# FE_Channel.net
KiCad netlist of a schematic drawn in Altium Designer
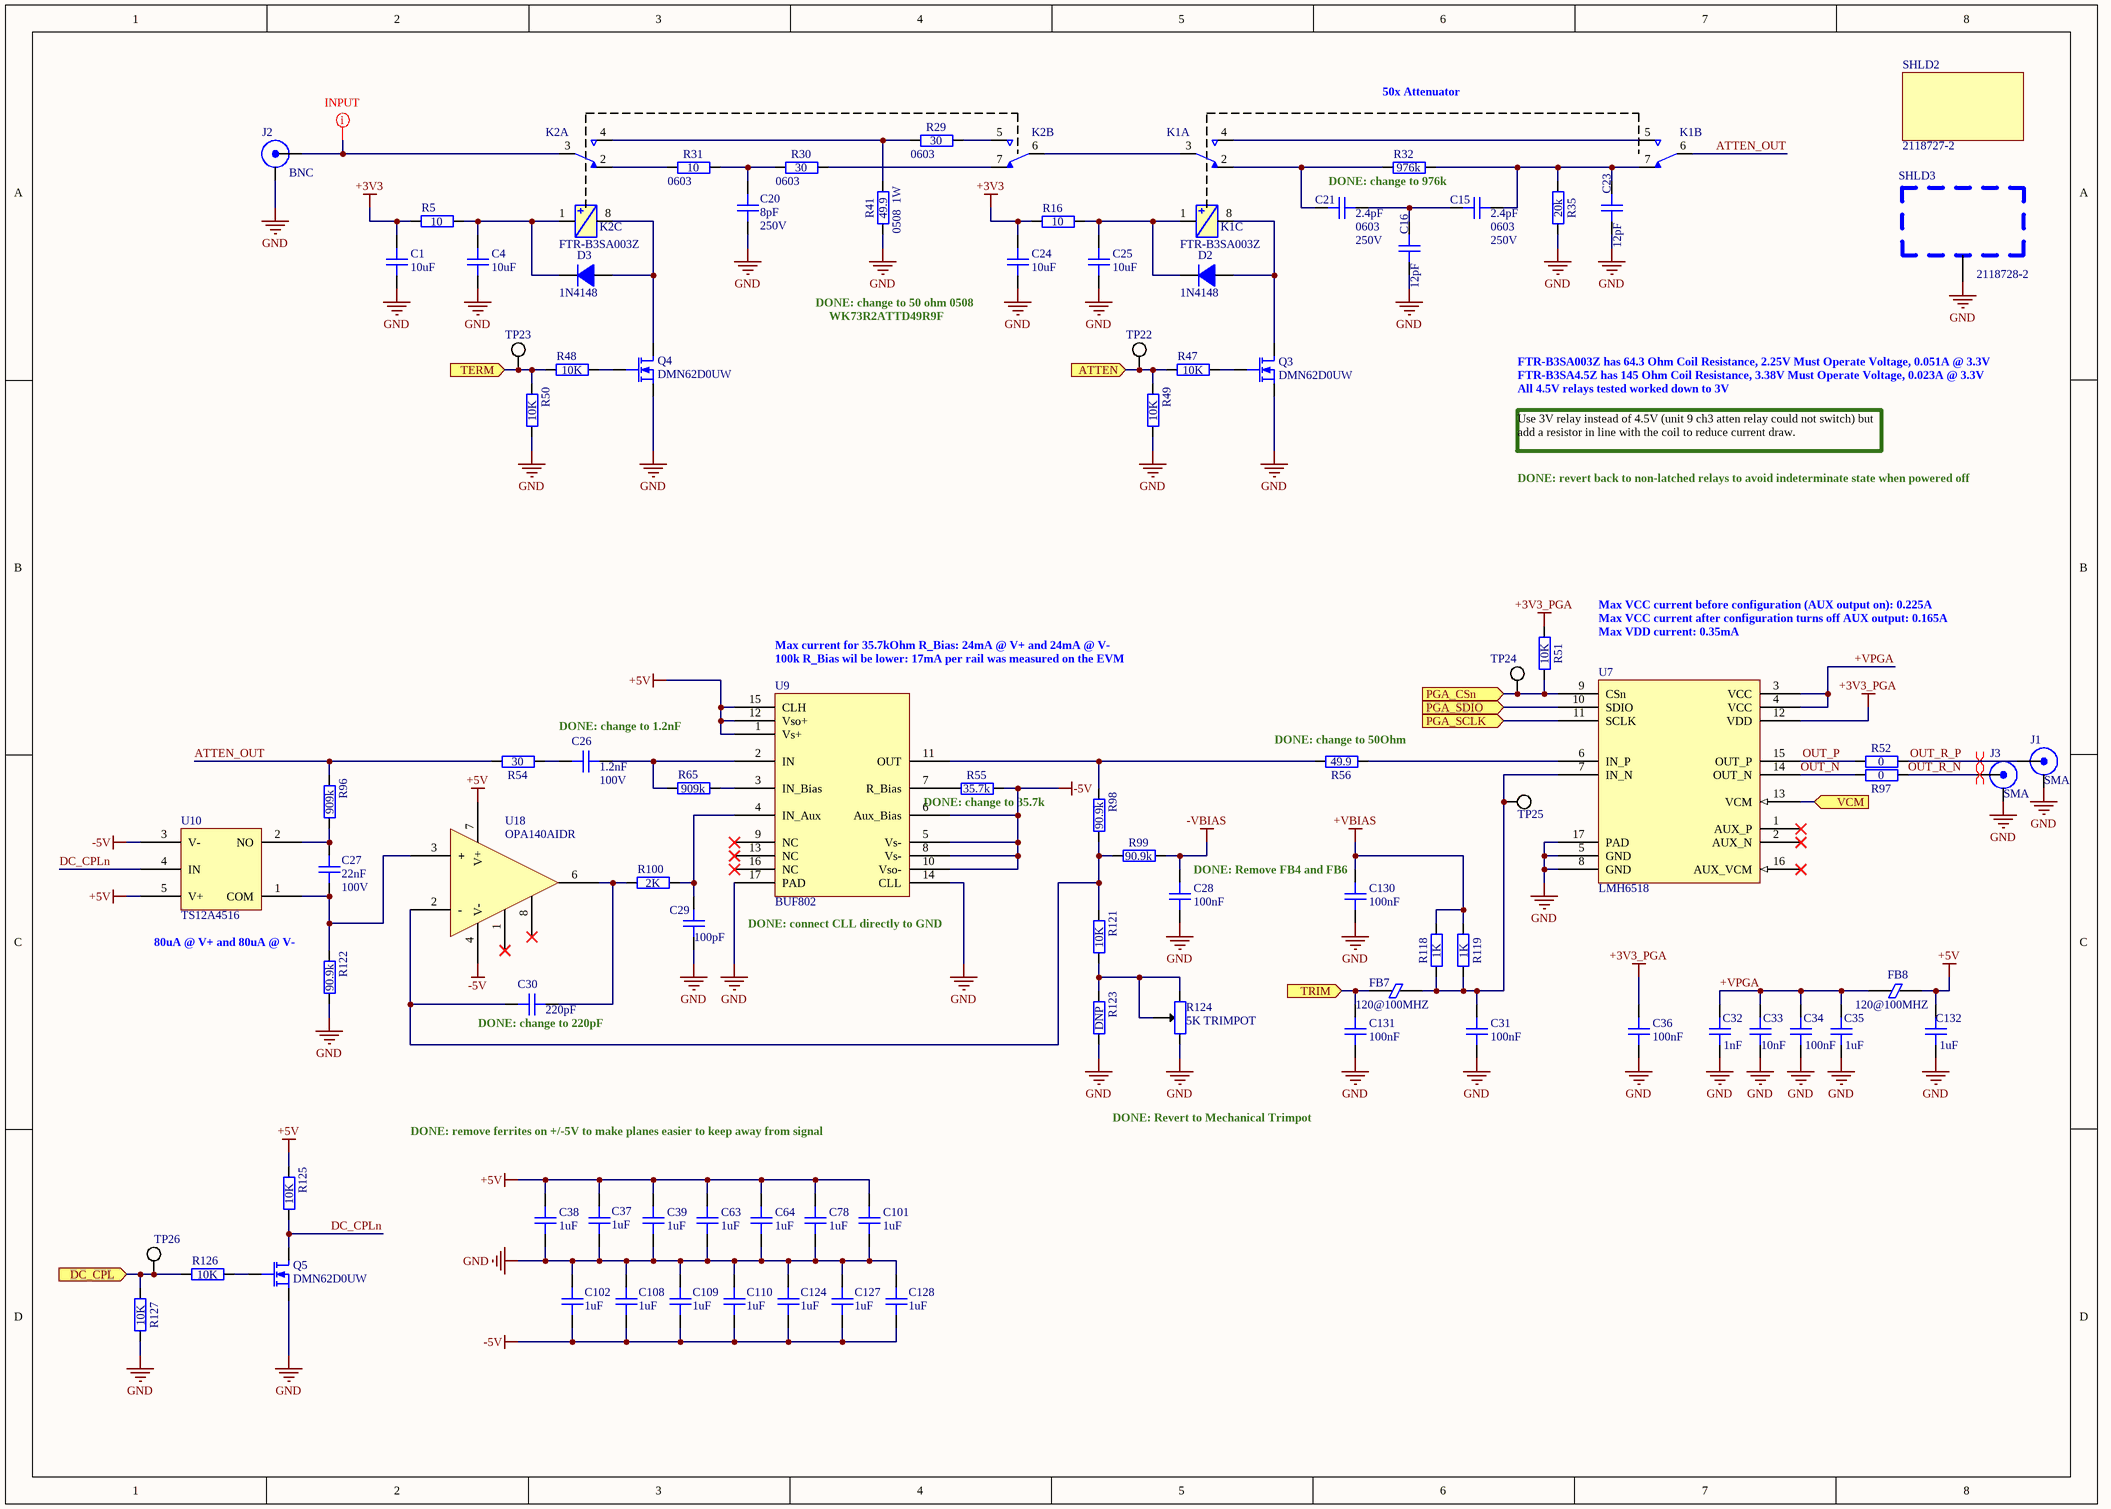
[diagram p0: FE_Channel.SchDoc]

(export (version "E")
  (design (tool "Eeschema 10.0.6"))
  (components
    (comp (ref "C1")
      (value "10uF")
      (footprint "GEN_C_0603")
      (fields
        (field (name "HOUSE PART NUMBER") "C-10uF-0603-002")
        (field (name "MANUFACTURER") "Murata")
        (field (name "MANUFACTURER PART NUMBER") "GRM188R61A106ME69D")
      )
      (libsource (lib "DSO") (part "CAP 10uF 10V X5R 0603"))
    )
    (comp (ref "C4")
      (value "10uF")
      (footprint "GEN_C_0603")
      (fields
        (field (name "HOUSE PART NUMBER") "C-10uF-0603-002")
        (field (name "MANUFACTURER") "Murata")
        (field (name "MANUFACTURER PART NUMBER") "GRM188R61A106ME69D")
      )
      (libsource (lib "DSO") (part "CAP 10uF 10V X5R 0603"))
    )
    (comp (ref "C15")
      (value "2.4pF")
      (footprint "GEN_C_0603")
      (fields
        (field (name "PACKAGE") "0603")
        (field (name "VOLTAGE RATING") "250V")
        (field (name "MANUFACTURER") "KEMET")
        (field (name "MANUFACTURER PART NUMBER") "CBR06C249BAGAC")
      )
      (libsource (lib "DSO") (part "CAP 2.4pF 250V C0G 0603"))
    )
    (comp (ref "C16")
      (value "12pF")
      (footprint "GEN_C_0402")
      (fields
        (field (name "MANUFACTURER") "KEMET")
        (field (name "MANUFACTURER PART NUMBER") "CBR04C120F5GAC")
      )
      (libsource (lib "DSO") (part "CAP 12pF 50V C0G 0402"))
    )
    (comp (ref "C20")
      (value "8pF")
      (footprint "GEN_C_0603")
      (fields
        (field (name "MANUFACTURER") "KEMET")
        (field (name "MANUFACTURER PART NUMBER") "CBR06C809BAGAC")
        (field (name "VOLTAGE RATING") "250V")
      )
      (libsource (lib "DSO") (part "CAP 8pF 250V C0G 0603"))
    )
    (comp (ref "C21")
      (value "2.4pF")
      (footprint "GEN_C_0603")
      (fields
        (field (name "PACKAGE") "0603")
        (field (name "VOLTAGE RATING") "250V")
        (field (name "MANUFACTURER") "KEMET")
        (field (name "MANUFACTURER PART NUMBER") "CBR06C249BAGAC")
      )
      (libsource (lib "DSO") (part "CAP 2.4pF 250V C0G 0603"))
    )
    (comp (ref "C23")
      (value "12pF")
      (footprint "GEN_C_0402")
      (fields
        (field (name "MANUFACTURER") "KEMET")
        (field (name "MANUFACTURER PART NUMBER") "CBR04C120F5GAC")
      )
      (libsource (lib "DSO") (part "CAP 12pF 50V C0G 0402"))
    )
    (comp (ref "C24")
      (value "10uF")
      (footprint "GEN_C_0603")
      (fields
        (field (name "HOUSE PART NUMBER") "C-10uF-0603-002")
        (field (name "MANUFACTURER") "Murata")
        (field (name "MANUFACTURER PART NUMBER") "GRM188R61A106ME69D")
      )
      (libsource (lib "DSO") (part "CAP 10uF 10V X5R 0603"))
    )
    (comp (ref "C25")
      (value "10uF")
      (footprint "GEN_C_0603")
      (fields
        (field (name "HOUSE PART NUMBER") "C-10uF-0603-002")
        (field (name "MANUFACTURER") "Murata")
        (field (name "MANUFACTURER PART NUMBER") "GRM188R61A106ME69D")
      )
      (libsource (lib "DSO") (part "CAP 10uF 10V X5R 0603"))
    )
    (comp (ref "C26")
      (value "1.2nF")
      (footprint "GEN_C_0603")
      (fields
        (field (name "VOLTAGE RATING") "100V")
        (field (name "MANUFACTURER") "Murata")
        (field (name "MANUFACTURER PART NUMBER") "GCM1885C2A122FA16D")
      )
      (libsource (lib "DSO") (part "CAP 1.2nF 100V C0G 0603"))
    )
    (comp (ref "C27")
      (value "22nF")
      (footprint "GEN_C_0603")
      (fields
        (field (name "VOLTAGE RATING") "100V")
        (field (name "MANUFACTURER") "Murata")
        (field (name "MANUFACTURER PART NUMBER") "GCM188R72A223KA37D")
      )
      (libsource (lib "DSO") (part "CAP 22nF 100V X7R 0603"))
    )
    (comp (ref "C28")
      (value "100nF")
      (footprint "GEN_C_0402")
      (fields
        (field (name "HOUSE PART NUMBER") "C-100nF-0402-002")
        (field (name "MANUFACTURER") "Murata")
        (field (name "MANUFACTURER PART NUMBER") "GCM155R71C104KA55D")
      )
      (libsource (lib "DSO") (part "CAP 100nF 16V X7R 0402"))
    )
    (comp (ref "C29")
      (value "100pF")
      (footprint "GEN_C_0402")
      (fields
        (field (name "MANUFACTURER") "Murata")
        (field (name "MANUFACTURER PART NUMBER") "GCM1555C1H101FA16D")
      )
      (libsource (lib "DSO") (part "CAP 100pF 50V C0G 0402"))
    )
    (comp (ref "C30")
      (value "220pF")
      (footprint "GEN_C_0402")
      (fields
        (field (name "MANUFACTURER") "Murata")
        (field (name "MANUFACTURER PART NUMBER") "GCM1555C1H221FA16J")
      )
      (libsource (lib "DSO") (part "CAP 220pF 50V C0G 0402"))
    )
    (comp (ref "C31")
      (value "100nF")
      (footprint "GEN_C_0402")
      (fields
        (field (name "HOUSE PART NUMBER") "C-100nF-0402-002")
        (field (name "MANUFACTURER") "Murata")
        (field (name "MANUFACTURER PART NUMBER") "GCM155R71C104KA55D")
      )
      (libsource (lib "DSO") (part "CAP 100nF 16V X7R 0402"))
    )
    (comp (ref "C32")
      (value "1nF")
      (footprint "GEN_C_0402")
      (fields
        (field (name "MANUFACTURER") "Murata")
        (field (name "MANUFACTURER PART NUMBER") "GRM1555C1H102FA01D")
      )
      (libsource (lib "DSO") (part "CAP 1nF 50V C0G 0402"))
    )
    (comp (ref "C33")
      (value "10nF")
      (footprint "GEN_C_0402")
      (fields
        (field (name "HOUSE PART NUMBER") "C-10nF-0402-002")
        (field (name "MANUFACTURER") "Murata")
        (field (name "MANUFACTURER PART NUMBER") "GRM155R71H103KA88J")
      )
      (libsource (lib "DSO") (part "CAP 10nF 50V X7R 0402"))
    )
    (comp (ref "C34")
      (value "100nF")
      (footprint "GEN_C_0402")
      (fields
        (field (name "HOUSE PART NUMBER") "C-100nF-0402-002")
        (field (name "MANUFACTURER") "Murata")
        (field (name "MANUFACTURER PART NUMBER") "GCM155R71C104KA55D")
      )
      (libsource (lib "DSO") (part "CAP 100nF 16V X7R 0402"))
    )
    (comp (ref "C35")
      (value "1uF")
      (footprint "GEN_C_0402")
      (fields
        (field (name "MANUFACTURER") "Murata")
        (field (name "MANUFACTURER PART NUMBER") "GRM155R61E105KA12D")
      )
      (libsource (lib "DSO") (part "CAP 1uF 25V X5R 0402"))
    )
    (comp (ref "C36")
      (value "100nF")
      (footprint "GEN_C_0402")
      (fields
        (field (name "HOUSE PART NUMBER") "C-100nF-0402-002")
        (field (name "MANUFACTURER") "Murata")
        (field (name "MANUFACTURER PART NUMBER") "GCM155R71C104KA55D")
      )
      (libsource (lib "DSO") (part "CAP 100nF 16V X7R 0402"))
    )
    (comp (ref "C37")
      (value "1uF")
      (footprint "GEN_C_0402")
      (fields
        (field (name "MANUFACTURER") "Murata")
        (field (name "MANUFACTURER PART NUMBER") "GRM155R61E105KA12D")
      )
      (libsource (lib "DSO") (part "CAP 1uF 25V X5R 0402"))
    )
    (comp (ref "C38")
      (value "1uF")
      (footprint "GEN_C_0402")
      (fields
        (field (name "MANUFACTURER") "Murata")
        (field (name "MANUFACTURER PART NUMBER") "GRM155R61E105KA12D")
      )
      (libsource (lib "DSO") (part "CAP 1uF 25V X5R 0402"))
    )
    (comp (ref "C39")
      (value "1uF")
      (footprint "GEN_C_0402")
      (fields
        (field (name "MANUFACTURER") "Murata")
        (field (name "MANUFACTURER PART NUMBER") "GRM155R61E105KA12D")
      )
      (libsource (lib "DSO") (part "CAP 1uF 25V X5R 0402"))
    )
    (comp (ref "C63")
      (value "1uF")
      (footprint "GEN_C_0402")
      (fields
        (field (name "MANUFACTURER") "Murata")
        (field (name "MANUFACTURER PART NUMBER") "GRM155R61E105KA12D")
      )
      (libsource (lib "DSO") (part "CAP 1uF 25V X5R 0402"))
    )
    (comp (ref "C64")
      (value "1uF")
      (footprint "GEN_C_0402")
      (fields
        (field (name "MANUFACTURER") "Murata")
        (field (name "MANUFACTURER PART NUMBER") "GRM155R61E105KA12D")
      )
      (libsource (lib "DSO") (part "CAP 1uF 25V X5R 0402"))
    )
    (comp (ref "C78")
      (value "1uF")
      (footprint "GEN_C_0402")
      (fields
        (field (name "MANUFACTURER") "Murata")
        (field (name "MANUFACTURER PART NUMBER") "GRM155R61E105KA12D")
      )
      (libsource (lib "DSO") (part "CAP 1uF 25V X5R 0402"))
    )
    (comp (ref "C101")
      (value "1uF")
      (footprint "GEN_C_0402")
      (fields
        (field (name "MANUFACTURER") "Murata")
        (field (name "MANUFACTURER PART NUMBER") "GRM155R61E105KA12D")
      )
      (libsource (lib "DSO") (part "CAP 1uF 25V X5R 0402"))
    )
    (comp (ref "C102")
      (value "1uF")
      (footprint "GEN_C_0402")
      (fields
        (field (name "MANUFACTURER") "Murata")
        (field (name "MANUFACTURER PART NUMBER") "GRM155R61E105KA12D")
      )
      (libsource (lib "DSO") (part "CAP 1uF 25V X5R 0402"))
    )
    (comp (ref "C108")
      (value "1uF")
      (footprint "GEN_C_0402")
      (fields
        (field (name "MANUFACTURER") "Murata")
        (field (name "MANUFACTURER PART NUMBER") "GRM155R61E105KA12D")
      )
      (libsource (lib "DSO") (part "CAP 1uF 25V X5R 0402"))
    )
    (comp (ref "C109")
      (value "1uF")
      (footprint "GEN_C_0402")
      (fields
        (field (name "MANUFACTURER") "Murata")
        (field (name "MANUFACTURER PART NUMBER") "GRM155R61E105KA12D")
      )
      (libsource (lib "DSO") (part "CAP 1uF 25V X5R 0402"))
    )
    (comp (ref "C110")
      (value "1uF")
      (footprint "GEN_C_0402")
      (fields
        (field (name "MANUFACTURER") "Murata")
        (field (name "MANUFACTURER PART NUMBER") "GRM155R61E105KA12D")
      )
      (libsource (lib "DSO") (part "CAP 1uF 25V X5R 0402"))
    )
    (comp (ref "C124")
      (value "1uF")
      (footprint "GEN_C_0402")
      (fields
        (field (name "MANUFACTURER") "Murata")
        (field (name "MANUFACTURER PART NUMBER") "GRM155R61E105KA12D")
      )
      (libsource (lib "DSO") (part "CAP 1uF 25V X5R 0402"))
    )
    (comp (ref "C127")
      (value "1uF")
      (footprint "GEN_C_0402")
      (fields
        (field (name "MANUFACTURER") "Murata")
        (field (name "MANUFACTURER PART NUMBER") "GRM155R61E105KA12D")
      )
      (libsource (lib "DSO") (part "CAP 1uF 25V X5R 0402"))
    )
    (comp (ref "C128")
      (value "1uF")
      (footprint "GEN_C_0402")
      (fields
        (field (name "MANUFACTURER") "Murata")
        (field (name "MANUFACTURER PART NUMBER") "GRM155R61E105KA12D")
      )
      (libsource (lib "DSO") (part "CAP 1uF 25V X5R 0402"))
    )
    (comp (ref "C130")
      (value "100nF")
      (footprint "GEN_C_0402")
      (fields
        (field (name "HOUSE PART NUMBER") "C-100nF-0402-002")
        (field (name "MANUFACTURER") "Murata")
        (field (name "MANUFACTURER PART NUMBER") "GCM155R71C104KA55D")
      )
      (libsource (lib "DSO") (part "CAP 100nF 16V X7R 0402"))
    )
    (comp (ref "C131")
      (value "100nF")
      (footprint "GEN_C_0402")
      (fields
        (field (name "HOUSE PART NUMBER") "C-100nF-0402-002")
        (field (name "MANUFACTURER") "Murata")
        (field (name "MANUFACTURER PART NUMBER") "GCM155R71C104KA55D")
      )
      (libsource (lib "DSO") (part "CAP 100nF 16V X7R 0402"))
    )
    (comp (ref "C132")
      (value "1uF")
      (footprint "GEN_C_0402")
      (fields
        (field (name "MANUFACTURER") "Murata")
        (field (name "MANUFACTURER PART NUMBER") "GRM155R61E105KA12D")
      )
      (libsource (lib "DSO") (part "CAP 1uF 25V X5R 0402"))
    )
    (comp (ref "D2")
      (value "1N4148")
      (footprint "GEN_SOD_323")
      (fields (field (name "MANUFACTURER") "Diodes") (field (name "MANUFACTURER PART NUMBER") "1N4148WS-7-F"))
      (libsource (lib "DSO") (part "DIODE 1N4148"))
    )
    (comp (ref "D3")
      (value "1N4148")
      (footprint "GEN_SOD_323")
      (fields (field (name "MANUFACTURER") "Diodes") (field (name "MANUFACTURER PART NUMBER") "1N4148WS-7-F"))
      (libsource (lib "DSO") (part "DIODE 1N4148"))
    )
    (comp (ref "FB7")
      (value "120@100MHZ")
      (footprint "GEN_R_0402")
      (fields (field (name "HOUSE PART NUMBER") "BLM15PX121SN1D") (field (name "MANUFACTURER") "Murata"))
      (libsource (lib "DSO") (part "FERRITE BEAD 120 OHM 0402"))
    )
    (comp (ref "FB8")
      (value "120@100MHZ")
      (footprint "GEN_R_0402")
      (fields (field (name "HOUSE PART NUMBER") "BLM15PX121SN1D") (field (name "MANUFACTURER") "Murata"))
      (libsource (lib "DSO") (part "FERRITE BEAD 120 OHM 0402"))
    )
    (comp (ref "J1")
      (value "SMA")
      (footprint "MOL_0733910083")
      (fields (field (name "MANUFACTURER") "Molex") (field (name "MANUFACTURER PART NUMBER") "73391-0083"))
      (libsource (lib "DSO") (part "SMA JACK R/A"))
    )
    (comp (ref "J2")
      (value "BNC")
      (footprint "MOL_0731000105")
      (fields (field (name "MANUFACTURER") "Molex") (field (name "MANUFACTURER PART NUMBER") "73100-0105"))
      (libsource (lib "DSO") (part "BNC JACK R/A"))
    )
    (comp (ref "J3")
      (value "SMA")
      (footprint "MOL_0733910083")
      (fields (field (name "MANUFACTURER") "Molex") (field (name "MANUFACTURER PART NUMBER") "73391-0083"))
      (libsource (lib "DSO") (part "SMA JACK R/A"))
    )
    (comp (ref "K1")
      (value "FTR-B3SA003Z")
      (footprint "FUJ_FTR-B3SA")
      (fields (field (name "MANUFACTURER") "Fujitsu"))
      (libsource (lib "") (part "RELAY DPDT-NO FTR-B3SA003Z_1"))
    )
    (comp (ref "K2")
      (value "FTR-B3SA003Z")
      (footprint "FUJ_FTR-B3SA")
      (fields (field (name "MANUFACTURER") "Fujitsu"))
      (libsource (lib "DSO") (part "RELAY DPDT-NO FTR-B3SA003Z"))
    )
    (comp (ref "Q3")
      (value "DMN62D0UW")
      (footprint "GEN_SOT_323")
      (fields (field (name "HOUSE PART NUMBER") "DMN62D0UW-7") (field (name "MANUFACTURER") "Diodes"))
      (libsource (lib "DSO") (part "NMOS DMN62D0UW"))
    )
    (comp (ref "Q4")
      (value "DMN62D0UW")
      (footprint "GEN_SOT_323")
      (fields (field (name "HOUSE PART NUMBER") "DMN62D0UW-7") (field (name "MANUFACTURER") "Diodes"))
      (libsource (lib "DSO") (part "NMOS DMN62D0UW"))
    )
    (comp (ref "Q5")
      (value "DMN62D0UW")
      (footprint "GEN_SOT_323")
      (fields (field (name "HOUSE PART NUMBER") "DMN62D0UW-7") (field (name "MANUFACTURER") "Diodes"))
      (libsource (lib "DSO") (part "NMOS DMN62D0UW"))
    )
    (comp (ref "R5")
      (value "10")
      (footprint "GEN_R_0603")
      (fields
        (field (name "TOLERANCE") "1%")
        (field (name "MANUFACTURER") "KOA Speer")
        (field (name "MANUFACTURER PART NUMBER") "SG73P1JTTD10R0F")
      )
      (libsource (lib "") (part "RES 10 OHM 1% 1/3W 0603_1"))
    )
    (comp (ref "R16")
      (value "10")
      (footprint "GEN_R_0603")
      (fields
        (field (name "TOLERANCE") "1%")
        (field (name "MANUFACTURER") "KOA Speer")
        (field (name "MANUFACTURER PART NUMBER") "SG73P1JTTD10R0F")
      )
      (libsource (lib "DSO") (part "RES 10 OHM 1% 1/3W 0603"))
    )
    (comp (ref "R29")
      (value "30")
      (footprint "GEN_R_0603")
      (fields
        (field (name "TOLERANCE") "1%")
        (field (name "PACKAGE") "0603")
        (field (name "MANUFACTURER") "KOA Speer")
        (field (name "MANUFACTURER PART NUMBER") "SG73P1JTTD30R0F")
      )
      (libsource (lib "DSO") (part "RES 30 OHM 1% 1/3W 0603"))
    )
    (comp (ref "R30")
      (value "30")
      (footprint "GEN_R_0603")
      (fields
        (field (name "TOLERANCE") "1%")
        (field (name "PACKAGE") "0603")
        (field (name "MANUFACTURER") "KOA Speer")
        (field (name "MANUFACTURER PART NUMBER") "SG73P1JTTD30R0F")
      )
      (libsource (lib "DSO") (part "RES 30 OHM 1% 1/3W 0603"))
    )
    (comp (ref "R31")
      (value "10")
      (footprint "GEN_R_0603")
      (fields
        (field (name "TOLERANCE") "1%")
        (field (name "PACKAGE") "0603")
        (field (name "MANUFACTURER") "KOA Speer")
        (field (name "MANUFACTURER PART NUMBER") "SG73P1JTTD10R0F")
      )
      (libsource (lib "DSO") (part "RES 10 OHM 1% 1/3W 0603"))
    )
    (comp (ref "R32")
      (value "976k")
      (footprint "GEN_R_0603")
      (fields
        (field (name "MANUFACTURER") "KOA Speer")
        (field (name "MANUFACTURER PART NUMBER") "RK73H1JTTD9763F")
        (field (name "TOLERANCE") "1%")
      )
      (libsource (lib "DSO") (part "RES 976k OHM 1% 1/10W 0603"))
    )
    (comp (ref "R35")
      (value "20k")
      (footprint "GEN_R_0402")
      (fields
        (field (name "TOLERANCE") "1%")
        (field (name "MANUFACTURER") "Yageo")
        (field (name "MANUFACTURER PART NUMBER") "RC0402FR-0720KL")
      )
      (libsource (lib "DSO") (part "RES 20K OHM 1% 1/16W 0402"))
    )
    (comp (ref "R41")
      (value "49.9")
      (footprint "GEN_R_0508")
      (fields
        (field (name "TOLERANCE") "1%")
        (field (name "PACKAGE") "0508")
        (field (name "MANUFACTURER") "KOA Speer")
        (field (name "MANUFACTURER PART NUMBER") "WK73R2ATTD49R9F")
        (field (name "POWER RATING") "1W")
      )
      (libsource (lib "DSO") (part "RES 49.9 OHM 1% 1W 0508"))
    )
    (comp (ref "R47")
      (value "10K")
      (footprint "GEN_R_0402")
      (fields
        (field (name "TOLERANCE") "1%")
        (field (name "MANUFACTURER") "Panasonic")
        (field (name "MANUFACTURER PART NUMBER") "ERJ-2RKF1002X")
      )
      (libsource (lib "DSO") (part "RES 10K OHM 1% 1/10W 0402"))
    )
    (comp (ref "R48")
      (value "10K")
      (footprint "GEN_R_0402")
      (fields
        (field (name "TOLERANCE") "1%")
        (field (name "MANUFACTURER") "Panasonic")
        (field (name "MANUFACTURER PART NUMBER") "ERJ-2RKF1002X")
      )
      (libsource (lib "DSO") (part "RES 10K OHM 1% 1/10W 0402"))
    )
    (comp (ref "R49")
      (value "10K")
      (footprint "GEN_R_0402")
      (fields
        (field (name "TOLERANCE") "1%")
        (field (name "MANUFACTURER") "Panasonic")
        (field (name "MANUFACTURER PART NUMBER") "ERJ-2RKF1002X")
      )
      (libsource (lib "") (part "RES 10K OHM 1% 1/10W 0402_1"))
    )
    (comp (ref "R50")
      (value "10K")
      (footprint "GEN_R_0402")
      (fields
        (field (name "TOLERANCE") "1%")
        (field (name "MANUFACTURER") "Panasonic")
        (field (name "MANUFACTURER PART NUMBER") "ERJ-2RKF1002X")
      )
      (libsource (lib "") (part "RES 10K OHM 1% 1/10W 0402_1"))
    )
    (comp (ref "R51")
      (value "10K")
      (footprint "GEN_R_0402")
      (fields
        (field (name "TOLERANCE") "1%")
        (field (name "MANUFACTURER") "Panasonic")
        (field (name "MANUFACTURER PART NUMBER") "ERJ-2RKF1002X")
      )
      (libsource (lib "") (part "RES 10K OHM 1% 1/10W 0402_1"))
    )
    (comp (ref "R52")
      (value "0")
      (footprint "GEN_R_0402")
      (fields
        (field (name "MANUFACTURER") "Yageo")
        (field (name "MANUFACTURER PART NUMBER") "RC0402JR-070RL")
      )
      (libsource (lib "DSO") (part "RES 0 OHM 1/16W 0402"))
    )
    (comp (ref "R54")
      (value "30")
      (footprint "GEN_R_0603")
      (fields
        (field (name "TOLERANCE") "1%")
        (field (name "MANUFACTURER") "KOA Speer")
        (field (name "MANUFACTURER PART NUMBER") "SG73P1JTTD30R0F")
      )
      (libsource (lib "DSO") (part "RES 30 OHM 1% 1/3W 0603"))
    )
    (comp (ref "R55")
      (value "35.7k")
      (footprint "GEN_R_0402")
      (fields
        (field (name "TOLERANCE") "1%")
        (field (name "MANUFACTURER") "Yageo")
        (field (name "MANUFACTURER PART NUMBER") "RC0402FR-0735K7L")
      )
      (libsource (lib "DSO") (part "RES 35.7K OHM 1% 1/16W 0402"))
    )
    (comp (ref "R56")
      (value "49.9")
      (footprint "GEN_R_0402")
      (fields
        (field (name "MANUFACTURER") "Yageo")
        (field (name "MANUFACTURER PART NUMBER") "RC0402FR-0749R9L")
        (field (name "TOLERANCE") "1%")
      )
      (libsource (lib "DSO") (part "RES 49.9 OHM 1% 1/10W 0402"))
    )
    (comp (ref "R65")
      (value "909k")
      (footprint "GEN_R_0402")
      (fields
        (field (name "TOLERANCE") "1%")
        (field (name "MANUFACTURER") "Yageo")
        (field (name "MANUFACTURER PART NUMBER") "RC0402FR-07909KL")
      )
      (libsource (lib "") (part "RES 909K OHM 1% 1/16W 0402_1"))
    )
    (comp (ref "R96")
      (value "909k")
      (footprint "GEN_R_0402")
      (fields
        (field (name "TOLERANCE") "1%")
        (field (name "MANUFACTURER") "Yageo")
        (field (name "MANUFACTURER PART NUMBER") "RC0402FR-07909KL")
      )
      (libsource (lib "DSO") (part "RES 909K OHM 1% 1/16W 0402"))
    )
    (comp (ref "R97")
      (value "0")
      (footprint "GEN_R_0402")
      (fields
        (field (name "MANUFACTURER") "Yageo")
        (field (name "MANUFACTURER PART NUMBER") "RC0402JR-070RL")
      )
      (libsource (lib "DSO") (part "RES 0 OHM 1/16W 0402"))
    )
    (comp (ref "R98")
      (value "90.9k")
      (footprint "GEN_R_0402")
      (fields
        (field (name "TOLERANCE") "1%")
        (field (name "MANUFACTURER") "Yageo")
        (field (name "MANUFACTURER PART NUMBER") "RC0402FR-0790K9L")
      )
      (libsource (lib "DSO") (part "RES 90.9K OHM 1% 1/16W 0402"))
    )
    (comp (ref "R99")
      (value "90.9k")
      (footprint "GEN_R_0402")
      (fields
        (field (name "TOLERANCE") "1%")
        (field (name "MANUFACTURER") "Yageo")
        (field (name "MANUFACTURER PART NUMBER") "RC0402FR-0790K9L")
      )
      (libsource (lib "") (part "RES 90.9K OHM 1% 1/16W 0402_1"))
    )
    (comp (ref "R100")
      (value "2K")
      (footprint "GEN_R_0402")
      (fields
        (field (name "TOLERANCE") "1%")
        (field (name "MANUFACTURER") "Yageo")
        (field (name "MANUFACTURER PART NUMBER") "RC0402FR-072KL")
      )
      (libsource (lib "DSO") (part "RES 2K OHM 1% 1/16W 0402"))
    )
    (comp (ref "R118")
      (value "1K")
      (footprint "GEN_R_0402")
      (fields
        (field (name "TOLERANCE") "1%")
        (field (name "HOUSE PART NUMBER") "R-1K-0402-1%-001")
        (field (name "MANUFACTURER") "Yageo")
      )
      (libsource (lib "DSO") (part "RES 1K OHM 1% 1/10W 0402"))
    )
    (comp (ref "R119")
      (value "1K")
      (footprint "GEN_R_0402")
      (fields
        (field (name "TOLERANCE") "1%")
        (field (name "HOUSE PART NUMBER") "R-1K-0402-1%-001")
        (field (name "MANUFACTURER") "Yageo")
      )
      (libsource (lib "") (part "RES 1K OHM 1% 1/10W 0402_1"))
    )
    (comp (ref "R121")
      (value "10K")
      (footprint "GEN_R_0402")
      (fields
        (field (name "TOLERANCE") "1%")
        (field (name "MANUFACTURER") "Panasonic")
        (field (name "MANUFACTURER PART NUMBER") "ERJ-2RKF1002X")
      )
      (libsource (lib "") (part "RES 10K OHM 1% 1/10W 0402_1"))
    )
    (comp (ref "R122")
      (value "90.9k")
      (footprint "GEN_R_0402")
      (fields
        (field (name "TOLERANCE") "1%")
        (field (name "MANUFACTURER") "Yageo")
        (field (name "MANUFACTURER PART NUMBER") "RC0402FR-0790K9L")
      )
      (libsource (lib "DSO") (part "RES 90.9K OHM 1% 1/16W 0402"))
    )
    (comp (ref "R123")
      (value "DNP")
      (footprint "GEN_R_0402")
      (fields (field (name "TOLERANCE") "1%"))
      (libsource (lib "DSO") (part "RES DNP 0402"))
    )
    (comp (ref "R124")
      (value "5K TRIMPOT")
      (footprint "BOU_3mm_POT")
      (fields
        (field (name "TOLERANCE") "1%")
        (field (name "MANUFACTURER") "Bourns")
        (field (name "MANUFACTURER PART NUMBER") "TC33X-2-502E")
      )
      (libsource (lib "DSO") (part "TRIMMER 5K OHM 0.1W J LEAD TOP"))
    )
    (comp (ref "R125")
      (value "10K")
      (footprint "GEN_R_0402")
      (fields
        (field (name "TOLERANCE") "1%")
        (field (name "MANUFACTURER") "Panasonic")
        (field (name "MANUFACTURER PART NUMBER") "ERJ-2RKF1002X")
      )
      (libsource (lib "") (part "RES 10K OHM 1% 1/10W 0402_1"))
    )
    (comp (ref "R126")
      (value "10K")
      (footprint "GEN_R_0402")
      (fields
        (field (name "TOLERANCE") "1%")
        (field (name "MANUFACTURER") "Panasonic")
        (field (name "MANUFACTURER PART NUMBER") "ERJ-2RKF1002X")
      )
      (libsource (lib "DSO") (part "RES 10K OHM 1% 1/10W 0402"))
    )
    (comp (ref "R127")
      (value "10K")
      (footprint "GEN_R_0402")
      (fields
        (field (name "TOLERANCE") "1%")
        (field (name "MANUFACTURER") "Panasonic")
        (field (name "MANUFACTURER PART NUMBER") "ERJ-2RKF1002X")
      )
      (libsource (lib "") (part "RES 10K OHM 1% 1/10W 0402_2"))
    )
    (comp (ref "SHLD2")
      (value "2118727-2")
      (fields (field (name "MANUFACTURER") "TE Connectivity AMP"))
      (libsource (lib "DSO") (part "SHIELD 2118727-2"))
    )
    (comp (ref "SHLD3")
      (value "2118728-2")
      (footprint "TE_2118728-2")
      (fields (field (name "MANUFACTURER") "TE Connectivity"))
      (libsource (lib "DSO") (part "SHIELD 2118728-2"))
    )
    (comp (ref "TP22") (value "PCB") (footprint "GEN_TP_PCB") (libsource (lib "DSO") (part "TP PCB 1mm")))
    (comp (ref "TP23") (value "PCB") (footprint "GEN_TP_PCB") (libsource (lib "DSO") (part "TP PCB 1mm")))
    (comp (ref "TP24") (value "PCB") (footprint "GEN_TP_PCB") (libsource (lib "DSO") (part "TP PCB 1mm")))
    (comp (ref "TP25") (value "PCB") (footprint "GEN_TP_PCB") (libsource (lib "DSO") (part "TP PCB 1mm")))
    (comp (ref "TP26") (value "PCB") (footprint "GEN_TP_PCB") (libsource (lib "DSO") (part "TP PCB 1mm")))
    (comp (ref "U7")
      (value "LMH6518")
      (footprint "TI_WQFN_RGH0016A")
      (fields
        (field (name "MANUFACTURER") "Texas Instruments")
        (field (name "MANUFACTURER PART NUMBER") "LMH6518SQE/NOPB")
      )
      (libsource (lib "DSO") (part "IC PGA LMH6518"))
    )
    (comp (ref "U9")
      (value "BUF802")
      (footprint "TI_VQFN_RGT0016C")
      (fields
        (field (name "MANUFACTURER") "Texas Instruments")
        (field (name "MANUFACTURER PART NUMBER") "BUF802IRGTR")
      )
      (libsource (lib "DSO") (part "IC BUFFER AMP BUF802"))
    )
    (comp (ref "U10")
      (value "TS12A4516")
      (footprint "GEN_SOT23_5_950_2900X1600X1450")
      (fields
        (field (name "MANUFACTURER") "Texas Instruments")
        (field (name "MANUFACTURER PART NUMBER") "TS12A4516DBVR")
      )
      (libsource (lib "DSO") (part "IC SWITCH SPST TS12A4516DBVR"))
    )
    (comp (ref "U18")
      (value "OPA140AIDR")
      (footprint "TI_SOIC8_D0008A")
      (fields (field (name "MANUFACTURER") "Texas Instruments"))
      (libsource (lib "DSO") (part "IC OPAMP OPA140"))
    )
  )
  (nets
    (net (code "1") (name "+3V3") (class "Default")
      (node (ref "C1") (pin "2") (pinfunction "2_2") (pintype "passive"))
      (node (ref "C24") (pin "2") (pinfunction "2_2") (pintype "passive"))
      (node (ref "R16") (pin "1") (pinfunction "1_1") (pintype "passive"))
      (node (ref "R5") (pin "2") (pinfunction "2_2") (pintype "passive"))
    )
    (net (code "2") (name "+3V3_PGA") (class "Default")
      (node (ref "C36") (pin "2") (pinfunction "2_2") (pintype "passive"))
      (node (ref "R51") (pin "2") (pinfunction "2_2") (pintype "passive"))
      (node (ref "U7") (pin "12") (pinfunction "VDD_12") (pintype "power_in"))
    )
    (net (code "3") (name "+5V") (class "Default")
      (node (ref "C101") (pin "2") (pinfunction "2_2") (pintype "passive"))
      (node (ref "C132") (pin "2") (pinfunction "2_2") (pintype "passive"))
      (node (ref "C37") (pin "2") (pinfunction "2_2") (pintype "passive"))
      (node (ref "C38") (pin "1") (pinfunction "1_1") (pintype "passive"))
      (node (ref "C39") (pin "1") (pinfunction "1_1") (pintype "passive"))
      (node (ref "C63") (pin "1") (pinfunction "1_1") (pintype "passive"))
      (node (ref "C64") (pin "2") (pinfunction "2_2") (pintype "passive"))
      (node (ref "C78") (pin "2") (pinfunction "2_2") (pintype "passive"))
      (node (ref "FB8") (pin "2") (pinfunction "2_2") (pintype "passive"))
      (node (ref "R125") (pin "2") (pinfunction "2_2") (pintype "passive"))
      (node (ref "U10") (pin "5") (pinfunction "V+_5") (pintype "passive"))
      (node (ref "U18") (pin "7") (pinfunction "V+_7") (pintype "passive"))
      (node (ref "U9") (pin "1") (pinfunction "Vs+_1") (pintype "passive"))
      (node (ref "U9") (pin "12") (pinfunction "Vso+_12") (pintype "passive"))
      (node (ref "U9") (pin "15") (pinfunction "CLH_15") (pintype "passive"))
    )
    (net (code "4") (name "+VBIAS") (class "Default")
      (node (ref "C130") (pin "1") (pinfunction "1_1") (pintype "passive"))
      (node (ref "R118") (pin "2") (pinfunction "2_2") (pintype "passive"))
      (node (ref "R119") (pin "1") (pinfunction "1_1") (pintype "passive"))
    )
    (net (code "5") (name "-5V") (class "Default")
      (node (ref "C102") (pin "2") (pinfunction "2_2") (pintype "passive"))
      (node (ref "C108") (pin "2") (pinfunction "2_2") (pintype "passive"))
      (node (ref "C109") (pin "1") (pinfunction "1_1") (pintype "passive"))
      (node (ref "C110") (pin "1") (pinfunction "1_1") (pintype "passive"))
      (node (ref "C124") (pin "1") (pinfunction "1_1") (pintype "passive"))
      (node (ref "C127") (pin "2") (pinfunction "2_2") (pintype "passive"))
      (node (ref "C128") (pin "2") (pinfunction "2_2") (pintype "passive"))
      (node (ref "R55") (pin "2") (pinfunction "2_2") (pintype "passive"))
      (node (ref "U10") (pin "3") (pinfunction "V-_3") (pintype "passive"))
      (node (ref "U18") (pin "4") (pinfunction "V-_4") (pintype "passive"))
      (node (ref "U9") (pin "10") (pinfunction "Vso-_10") (pintype "passive"))
      (node (ref "U9") (pin "5") (pinfunction "Vs-_5") (pintype "passive"))
      (node (ref "U9") (pin "6") (pinfunction "Aux_Bias_6") (pintype "passive"))
      (node (ref "U9") (pin "8") (pinfunction "Vs-_8") (pintype "passive"))
    )
    (net (code "6") (name "-VBIAS") (class "Default")
      (node (ref "C28") (pin "1") (pinfunction "1_1") (pintype "passive"))
      (node (ref "R99") (pin "1") (pinfunction "1_1") (pintype "passive"))
    )
    (net (code "7") (name "/+VPGA") (class "Default")
      (node (ref "C32") (pin "2") (pinfunction "2_2") (pintype "passive"))
      (node (ref "C33") (pin "2") (pinfunction "2_2") (pintype "passive"))
      (node (ref "C34") (pin "2") (pinfunction "2_2") (pintype "passive"))
      (node (ref "C35") (pin "2") (pinfunction "2_2") (pintype "passive"))
      (node (ref "FB8") (pin "1") (pinfunction "1_1") (pintype "passive"))
      (node (ref "U7") (pin "3") (pinfunction "VCC_3") (pintype "power_in"))
      (node (ref "U7") (pin "4") (pinfunction "VCC_4") (pintype "power_in"))
    )
    (net (code "8") (name "/ATTEN") (class "Default")
      (node (ref "R47") (pin "2") (pinfunction "2_2") (pintype "passive"))
      (node (ref "R49") (pin "2") (pinfunction "2_2") (pintype "passive"))
      (node (ref "TP22") (pin "1") (pinfunction "1_1") (pintype "passive"))
    )
    (net (code "9") (name "/ATTEN_OUT") (class "Default")
      (node (ref "K1") (pin "6") (pinfunction "6_6") (pintype "passive"))
      (node (ref "R54") (pin "1") (pinfunction "1_1") (pintype "passive"))
      (node (ref "R96") (pin "2") (pinfunction "2_2") (pintype "passive"))
    )
    (net (code "10") (name "/DC_CPL") (class "Default")
      (node (ref "R126") (pin "2") (pinfunction "2_2") (pintype "passive"))
      (node (ref "R127") (pin "2") (pinfunction "2_2") (pintype "passive"))
      (node (ref "TP26") (pin "1") (pinfunction "1_1") (pintype "passive"))
    )
    (net (code "11") (name "/DC_CPLn") (class "Default")
      (node (ref "Q5") (pin "1") (pinfunction "D_1") (pintype "passive"))
      (node (ref "R125") (pin "1") (pinfunction "1_1") (pintype "passive"))
      (node (ref "U10") (pin "4") (pinfunction "IN_4") (pintype "passive"))
    )
    (net (code "12") (name "/OUT_N") (class "Default")
      (node (ref "R97") (pin "1") (pinfunction "1_1") (pintype "passive"))
      (node (ref "U7") (pin "14") (pinfunction "OUT_N_14") (pintype "passive"))
    )
    (net (code "13") (name "/OUT_P") (class "Default")
      (node (ref "R52") (pin "1") (pinfunction "1_1") (pintype "passive"))
      (node (ref "U7") (pin "15") (pinfunction "OUT_P_15") (pintype "passive"))
    )
    (net (code "14") (name "/OUT_R_N") (class "Default")
      (node (ref "J3") (pin "1") (pinfunction "Signal_1") (pintype "passive"))
      (node (ref "R97") (pin "2") (pinfunction "2_2") (pintype "passive"))
    )
    (net (code "15") (name "/OUT_R_P") (class "Default")
      (node (ref "J1") (pin "1") (pinfunction "Signal_1") (pintype "passive"))
      (node (ref "R52") (pin "2") (pinfunction "2_2") (pintype "passive"))
    )
    (net (code "16") (name "/PGA_CSn") (class "Default")
      (node (ref "R51") (pin "1") (pinfunction "1_1") (pintype "passive"))
      (node (ref "TP24") (pin "1") (pinfunction "1_1") (pintype "passive"))
      (node (ref "U7") (pin "9") (pinfunction "CSn_9") (pintype "passive"))
    )
    (net (code "17") (name "/PGA_SCLK") (class "Default")
      (node (ref "U7") (pin "11") (pinfunction "SCLK_11") (pintype "passive"))
    )
    (net (code "18") (name "/PGA_SDIO") (class "Default")
      (node (ref "U7") (pin "10") (pinfunction "SDIO_10") (pintype "passive"))
    )
    (net (code "19") (name "/TERM") (class "Default")
      (node (ref "R48") (pin "2") (pinfunction "2_2") (pintype "passive"))
      (node (ref "R50") (pin "2") (pinfunction "2_2") (pintype "passive"))
      (node (ref "TP23") (pin "1") (pinfunction "1_1") (pintype "passive"))
    )
    (net (code "20") (name "/TRIM") (class "Default")
      (node (ref "C131") (pin "1") (pinfunction "1_1") (pintype "passive"))
      (node (ref "FB7") (pin "1") (pinfunction "1_1") (pintype "passive"))
    )
    (net (code "21") (name "/VCM") (class "Default")
      (node (ref "U7") (pin "13") (pinfunction "VCM_13") (pintype "input"))
    )
    (net (code "22") (name "GND") (class "Default")
      (node (ref "C1") (pin "1") (pinfunction "1_1") (pintype "passive"))
      (node (ref "C101") (pin "1") (pinfunction "1_1") (pintype "passive"))
      (node (ref "C102") (pin "1") (pinfunction "1_1") (pintype "passive"))
      (node (ref "C108") (pin "1") (pinfunction "1_1") (pintype "passive"))
      (node (ref "C109") (pin "2") (pinfunction "2_2") (pintype "passive"))
      (node (ref "C110") (pin "2") (pinfunction "2_2") (pintype "passive"))
      (node (ref "C124") (pin "2") (pinfunction "2_2") (pintype "passive"))
      (node (ref "C127") (pin "1") (pinfunction "1_1") (pintype "passive"))
      (node (ref "C128") (pin "1") (pinfunction "1_1") (pintype "passive"))
      (node (ref "C130") (pin "2") (pinfunction "2_2") (pintype "passive"))
      (node (ref "C131") (pin "2") (pinfunction "2_2") (pintype "passive"))
      (node (ref "C132") (pin "1") (pinfunction "1_1") (pintype "passive"))
      (node (ref "C16") (pin "1") (pinfunction "1_1") (pintype "passive"))
      (node (ref "C20") (pin "2") (pinfunction "2_2") (pintype "passive"))
      (node (ref "C23") (pin "1") (pinfunction "1_1") (pintype "passive"))
      (node (ref "C24") (pin "1") (pinfunction "1_1") (pintype "passive"))
      (node (ref "C25") (pin "1") (pinfunction "1_1") (pintype "passive"))
      (node (ref "C28") (pin "2") (pinfunction "2_2") (pintype "passive"))
      (node (ref "C29") (pin "1") (pinfunction "1_1") (pintype "passive"))
      (node (ref "C31") (pin "2") (pinfunction "2_2") (pintype "passive"))
      (node (ref "C32") (pin "1") (pinfunction "1_1") (pintype "passive"))
      (node (ref "C33") (pin "1") (pinfunction "1_1") (pintype "passive"))
      (node (ref "C34") (pin "1") (pinfunction "1_1") (pintype "passive"))
      (node (ref "C35") (pin "1") (pinfunction "1_1") (pintype "passive"))
      (node (ref "C36") (pin "1") (pinfunction "1_1") (pintype "passive"))
      (node (ref "C37") (pin "1") (pinfunction "1_1") (pintype "passive"))
      (node (ref "C38") (pin "2") (pinfunction "2_2") (pintype "passive"))
      (node (ref "C39") (pin "2") (pinfunction "2_2") (pintype "passive"))
      (node (ref "C4") (pin "1") (pinfunction "1_1") (pintype "passive"))
      (node (ref "C63") (pin "2") (pinfunction "2_2") (pintype "passive"))
      (node (ref "C64") (pin "1") (pinfunction "1_1") (pintype "passive"))
      (node (ref "C78") (pin "1") (pinfunction "1_1") (pintype "passive"))
      (node (ref "J1") (pin "2") (pinfunction "SHIELD_2") (pintype "passive"))
      (node (ref "J2") (pin "2") (pinfunction "SHIELD_2") (pintype "passive"))
      (node (ref "J3") (pin "2") (pinfunction "SHIELD_2") (pintype "passive"))
      (node (ref "Q3") (pin "3") (pinfunction "S_3") (pintype "passive"))
      (node (ref "Q4") (pin "3") (pinfunction "S_3") (pintype "passive"))
      (node (ref "Q5") (pin "3") (pinfunction "S_3") (pintype "passive"))
      (node (ref "R122") (pin "1") (pinfunction "1_1") (pintype "passive"))
      (node (ref "R123") (pin "1") (pinfunction "1_1") (pintype "passive"))
      (node (ref "R124") (pin "3") (pinfunction "3_3") (pintype "passive"))
      (node (ref "R127") (pin "1") (pinfunction "1_1") (pintype "passive"))
      (node (ref "R35") (pin "1") (pinfunction "1_1") (pintype "passive"))
      (node (ref "R41") (pin "1") (pinfunction "1_1") (pintype "passive"))
      (node (ref "R49") (pin "1") (pinfunction "1_1") (pintype "passive"))
      (node (ref "R50") (pin "1") (pinfunction "1_1") (pintype "passive"))
      (node (ref "SHLD3") (pin "1") (pinfunction "1_1") (pintype "passive"))
      (node (ref "U7") (pin "17") (pinfunction "PAD_17") (pintype "power_in"))
      (node (ref "U7") (pin "5") (pinfunction "GND_5") (pintype "power_in"))
      (node (ref "U7") (pin "8") (pinfunction "GND_8") (pintype "power_in"))
      (node (ref "U9") (pin "14") (pinfunction "CLL_14") (pintype "passive"))
      (node (ref "U9") (pin "17") (pinfunction "PAD_17") (pintype "passive"))
    )
    (net (code "23") (name "Net-(C15-Pad1)") (class "Default")
      (node (ref "C15") (pin "1") (pinfunction "1_1") (pintype "passive"))
      (node (ref "C23") (pin "2") (pinfunction "2_2") (pintype "passive"))
      (node (ref "K1") (pin "7") (pinfunction "7_7") (pintype "passive"))
      (node (ref "R32") (pin "2") (pinfunction "2_2") (pintype "passive"))
      (node (ref "R35") (pin "2") (pinfunction "2_2") (pintype "passive"))
    )
    (net (code "24") (name "Net-(C15-Pad2)") (class "Default")
      (node (ref "C15") (pin "2") (pinfunction "2_2") (pintype "passive"))
      (node (ref "C16") (pin "2") (pinfunction "2_2") (pintype "passive"))
      (node (ref "C21") (pin "1") (pinfunction "1_1") (pintype "passive"))
    )
    (net (code "25") (name "Net-(C20-Pad1)") (class "Default")
      (node (ref "C20") (pin "1") (pinfunction "1_1") (pintype "passive"))
      (node (ref "R30") (pin "1") (pinfunction "1_1") (pintype "passive"))
      (node (ref "R31") (pin "2") (pinfunction "2_2") (pintype "passive"))
    )
    (net (code "26") (name "Net-(C21-Pad2)") (class "Default")
      (node (ref "C21") (pin "2") (pinfunction "2_2") (pintype "passive"))
      (node (ref "K1") (pin "2") (pinfunction "2_2") (pintype "passive"))
      (node (ref "R32") (pin "1") (pinfunction "1_1") (pintype "passive"))
    )
    (net (code "27") (name "Net-(C26-Pad2)") (class "Default")
      (node (ref "C26") (pin "2") (pinfunction "2_2") (pintype "passive"))
      (node (ref "R54") (pin "2") (pinfunction "2_2") (pintype "passive"))
    )
    (net (code "28") (name "Net-(D2-A)") (class "Default")
      (node (ref "D2") (pin "2") (pinfunction "A_2") (pintype "passive"))
      (node (ref "K1") (pin "8") (pinfunction "8_8") (pintype "passive"))
      (node (ref "Q3") (pin "1") (pinfunction "D_1") (pintype "passive"))
    )
    (net (code "29") (name "Net-(D2-K)") (class "Default")
      (node (ref "C25") (pin "2") (pinfunction "2_2") (pintype "passive"))
      (node (ref "D2") (pin "1") (pinfunction "K_1") (pintype "passive"))
      (node (ref "K1") (pin "1") (pinfunction "1_1") (pintype "passive"))
      (node (ref "R16") (pin "2") (pinfunction "2_2") (pintype "passive"))
    )
    (net (code "30") (name "Net-(D3-A)") (class "Default")
      (node (ref "D3") (pin "2") (pinfunction "A_2") (pintype "passive"))
      (node (ref "K2") (pin "8") (pinfunction "8_8") (pintype "passive"))
      (node (ref "Q4") (pin "1") (pinfunction "D_1") (pintype "passive"))
    )
    (net (code "31") (name "Net-(D3-K)") (class "Default")
      (node (ref "C4") (pin "2") (pinfunction "2_2") (pintype "passive"))
      (node (ref "D3") (pin "1") (pinfunction "K_1") (pintype "passive"))
      (node (ref "K2") (pin "1") (pinfunction "1_1") (pintype "passive"))
      (node (ref "R5") (pin "1") (pinfunction "1_1") (pintype "passive"))
    )
    (net (code "32") (name "Net-(J2-Signal)") (class "Default")
      (node (ref "J2") (pin "1") (pinfunction "Signal_1") (pintype "passive"))
      (node (ref "K2") (pin "3") (pinfunction "3_3") (pintype "passive"))
    )
    (net (code "33") (name "Net-(K1-Pad3)") (class "Default")
      (node (ref "K1") (pin "3") (pinfunction "3_3") (pintype "passive"))
      (node (ref "K2") (pin "6") (pinfunction "6_6") (pintype "passive"))
    )
    (net (code "34") (name "Net-(K1-Pad4)") (class "Default")
      (node (ref "K1") (pin "4") (pinfunction "4_4") (pintype "passive"))
      (node (ref "K1") (pin "5") (pinfunction "5_5") (pintype "passive"))
    )
    (net (code "35") (name "Net-(K2-Pad2)") (class "Default")
      (node (ref "K2") (pin "2") (pinfunction "2_2") (pintype "passive"))
      (node (ref "R31") (pin "1") (pinfunction "1_1") (pintype "passive"))
    )
    (net (code "36") (name "Net-(K2-Pad4)") (class "Default")
      (node (ref "K2") (pin "4") (pinfunction "4_4") (pintype "passive"))
      (node (ref "R29") (pin "1") (pinfunction "1_1") (pintype "passive"))
      (node (ref "R41") (pin "2") (pinfunction "2_2") (pintype "passive"))
    )
    (net (code "37") (name "Net-(K2-Pad5)") (class "Default")
      (node (ref "K2") (pin "5") (pinfunction "5_5") (pintype "passive"))
      (node (ref "R29") (pin "2") (pinfunction "2_2") (pintype "passive"))
    )
    (net (code "38") (name "Net-(K2-Pad7)") (class "Default")
      (node (ref "K2") (pin "7") (pinfunction "7_7") (pintype "passive"))
      (node (ref "R30") (pin "2") (pinfunction "2_2") (pintype "passive"))
    )
    (net (code "39") (name "Net-(Q3-G)") (class "Default")
      (node (ref "Q3") (pin "2") (pinfunction "G_2") (pintype "passive"))
      (node (ref "R47") (pin "1") (pinfunction "1_1") (pintype "passive"))
    )
    (net (code "40") (name "Net-(Q4-G)") (class "Default")
      (node (ref "Q4") (pin "2") (pinfunction "G_2") (pintype "passive"))
      (node (ref "R48") (pin "1") (pinfunction "1_1") (pintype "passive"))
    )
    (net (code "41") (name "Net-(Q5-G)") (class "Default")
      (node (ref "Q5") (pin "2") (pinfunction "G_2") (pintype "passive"))
      (node (ref "R126") (pin "1") (pinfunction "1_1") (pintype "passive"))
    )
    (net (code "42") (name "Net-(R121-Pad1)") (class "Default")
      (node (ref "R121") (pin "1") (pinfunction "1_1") (pintype "passive"))
      (node (ref "R123") (pin "2") (pinfunction "2_2") (pintype "passive"))
      (node (ref "R124") (pin "1") (pinfunction "1_1") (pintype "passive"))
      (node (ref "R124") (pin "2") (pinfunction "2_2") (pintype "passive"))
    )
    (net (code "43") (name "Net-(U7-IN_N)") (class "Default")
      (node (ref "C31") (pin "1") (pinfunction "1_1") (pintype "passive"))
      (node (ref "FB7") (pin "2") (pinfunction "2_2") (pintype "passive"))
      (node (ref "R118") (pin "1") (pinfunction "1_1") (pintype "passive"))
      (node (ref "R119") (pin "2") (pinfunction "2_2") (pintype "passive"))
      (node (ref "TP25") (pin "1") (pinfunction "1_1") (pintype "passive"))
      (node (ref "U7") (pin "7") (pinfunction "IN_N_7") (pintype "passive"))
    )
    (net (code "44") (name "Net-(U7-IN_P)") (class "Default")
      (node (ref "R56") (pin "2") (pinfunction "2_2") (pintype "passive"))
      (node (ref "U7") (pin "6") (pinfunction "IN_P_6") (pintype "passive"))
    )
    (net (code "45") (name "Net-(U9-IN)") (class "Default")
      (node (ref "C26") (pin "1") (pinfunction "1_1") (pintype "passive"))
      (node (ref "R65") (pin "2") (pinfunction "2_2") (pintype "passive"))
      (node (ref "U9") (pin "2") (pinfunction "IN_2") (pintype "passive"))
    )
    (net (code "46") (name "Net-(U9-IN_Aux)") (class "Default")
      (node (ref "C29") (pin "2") (pinfunction "2_2") (pintype "passive"))
      (node (ref "R100") (pin "1") (pinfunction "1_1") (pintype "passive"))
      (node (ref "U9") (pin "4") (pinfunction "IN_Aux_4") (pintype "passive"))
    )
    (net (code "47") (name "Net-(U9-IN_Bias)") (class "Default")
      (node (ref "R65") (pin "1") (pinfunction "1_1") (pintype "passive"))
      (node (ref "U9") (pin "3") (pinfunction "IN_Bias_3") (pintype "passive"))
    )
    (net (code "48") (name "Net-(U9-OUT)") (class "Default")
      (node (ref "R56") (pin "1") (pinfunction "1_1") (pintype "passive"))
      (node (ref "R98") (pin "2") (pinfunction "2_2") (pintype "passive"))
      (node (ref "U9") (pin "11") (pinfunction "OUT_11") (pintype "passive"))
    )
    (net (code "49") (name "Net-(U9-R_Bias)") (class "Default")
      (node (ref "R55") (pin "1") (pinfunction "1_1") (pintype "passive"))
      (node (ref "U9") (pin "7") (pinfunction "R_Bias_7") (pintype "passive"))
    )
    (net (code "50") (name "Net-(U10-COM)") (class "Default")
      (node (ref "C27") (pin "2") (pinfunction "2_2") (pintype "passive"))
      (node (ref "R122") (pin "2") (pinfunction "2_2") (pintype "passive"))
      (node (ref "U10") (pin "1") (pinfunction "COM_1") (pintype "passive"))
      (node (ref "U18") (pin "3") (pinfunction "+_3") (pintype "passive"))
    )
    (net (code "51") (name "Net-(U10-NO)") (class "Default")
      (node (ref "C27") (pin "1") (pinfunction "1_1") (pintype "passive"))
      (node (ref "R96") (pin "1") (pinfunction "1_1") (pintype "passive"))
      (node (ref "U10") (pin "2") (pinfunction "NO_2") (pintype "passive"))
    )
    (net (code "52") (name "Net-(U18--)") (class "Default")
      (node (ref "C30") (pin "2") (pinfunction "2_2") (pintype "passive"))
      (node (ref "R121") (pin "2") (pinfunction "2_2") (pintype "passive"))
      (node (ref "R98") (pin "1") (pinfunction "1_1") (pintype "passive"))
      (node (ref "R99") (pin "2") (pinfunction "2_2") (pintype "passive"))
      (node (ref "U18") (pin "2") (pinfunction "-_2") (pintype "passive"))
    )
    (net (code "53") (name "Net-(U18-OUT)") (class "Default")
      (node (ref "C30") (pin "1") (pinfunction "1_1") (pintype "passive"))
      (node (ref "R100") (pin "2") (pinfunction "2_2") (pintype "passive"))
      (node (ref "U18") (pin "6") (pinfunction "OUT_6") (pintype "passive"))
    )
    (net (code "54") (name "unconnected-(U7-AUX_N-Pad2)") (class "Default")
      (node (ref "U7") (pin "2") (pinfunction "AUX_N_2") (pintype "passive+no_connect"))
    )
    (net (code "55") (name "unconnected-(U7-AUX_P-Pad1)") (class "Default")
      (node (ref "U7") (pin "1") (pinfunction "AUX_P_1") (pintype "passive+no_connect"))
    )
    (net (code "56") (name "unconnected-(U7-AUX_VCM-Pad16)") (class "Default")
      (node (ref "U7") (pin "16") (pinfunction "AUX_VCM_16") (pintype "input+no_connect"))
    )
    (net (code "57") (name "unconnected-(U9-NC-Pad9)") (class "Default")
      (node (ref "U9") (pin "9") (pinfunction "NC_9") (pintype "passive+no_connect"))
    )
    (net (code "58") (name "unconnected-(U9-NC-Pad13)") (class "Default")
      (node (ref "U9") (pin "13") (pinfunction "NC_13") (pintype "passive+no_connect"))
    )
    (net (code "59") (name "unconnected-(U9-NC-Pad16)") (class "Default")
      (node (ref "U9") (pin "16") (pinfunction "NC_16") (pintype "passive+no_connect"))
    )
    (net (code "60") (name "unconnected-(U18-N1-Pad1)") (class "Default")
      (node (ref "U18") (pin "1") (pinfunction "N1_1") (pintype "passive+no_connect"))
    )
    (net (code "61") (name "unconnected-(U18-N2-Pad8)") (class "Default")
      (node (ref "U18") (pin "8") (pinfunction "N2_8") (pintype "passive+no_connect"))
    )
  )
)
